# usbHub.net
KiCad netlist of a schematic drawn in EAGLE
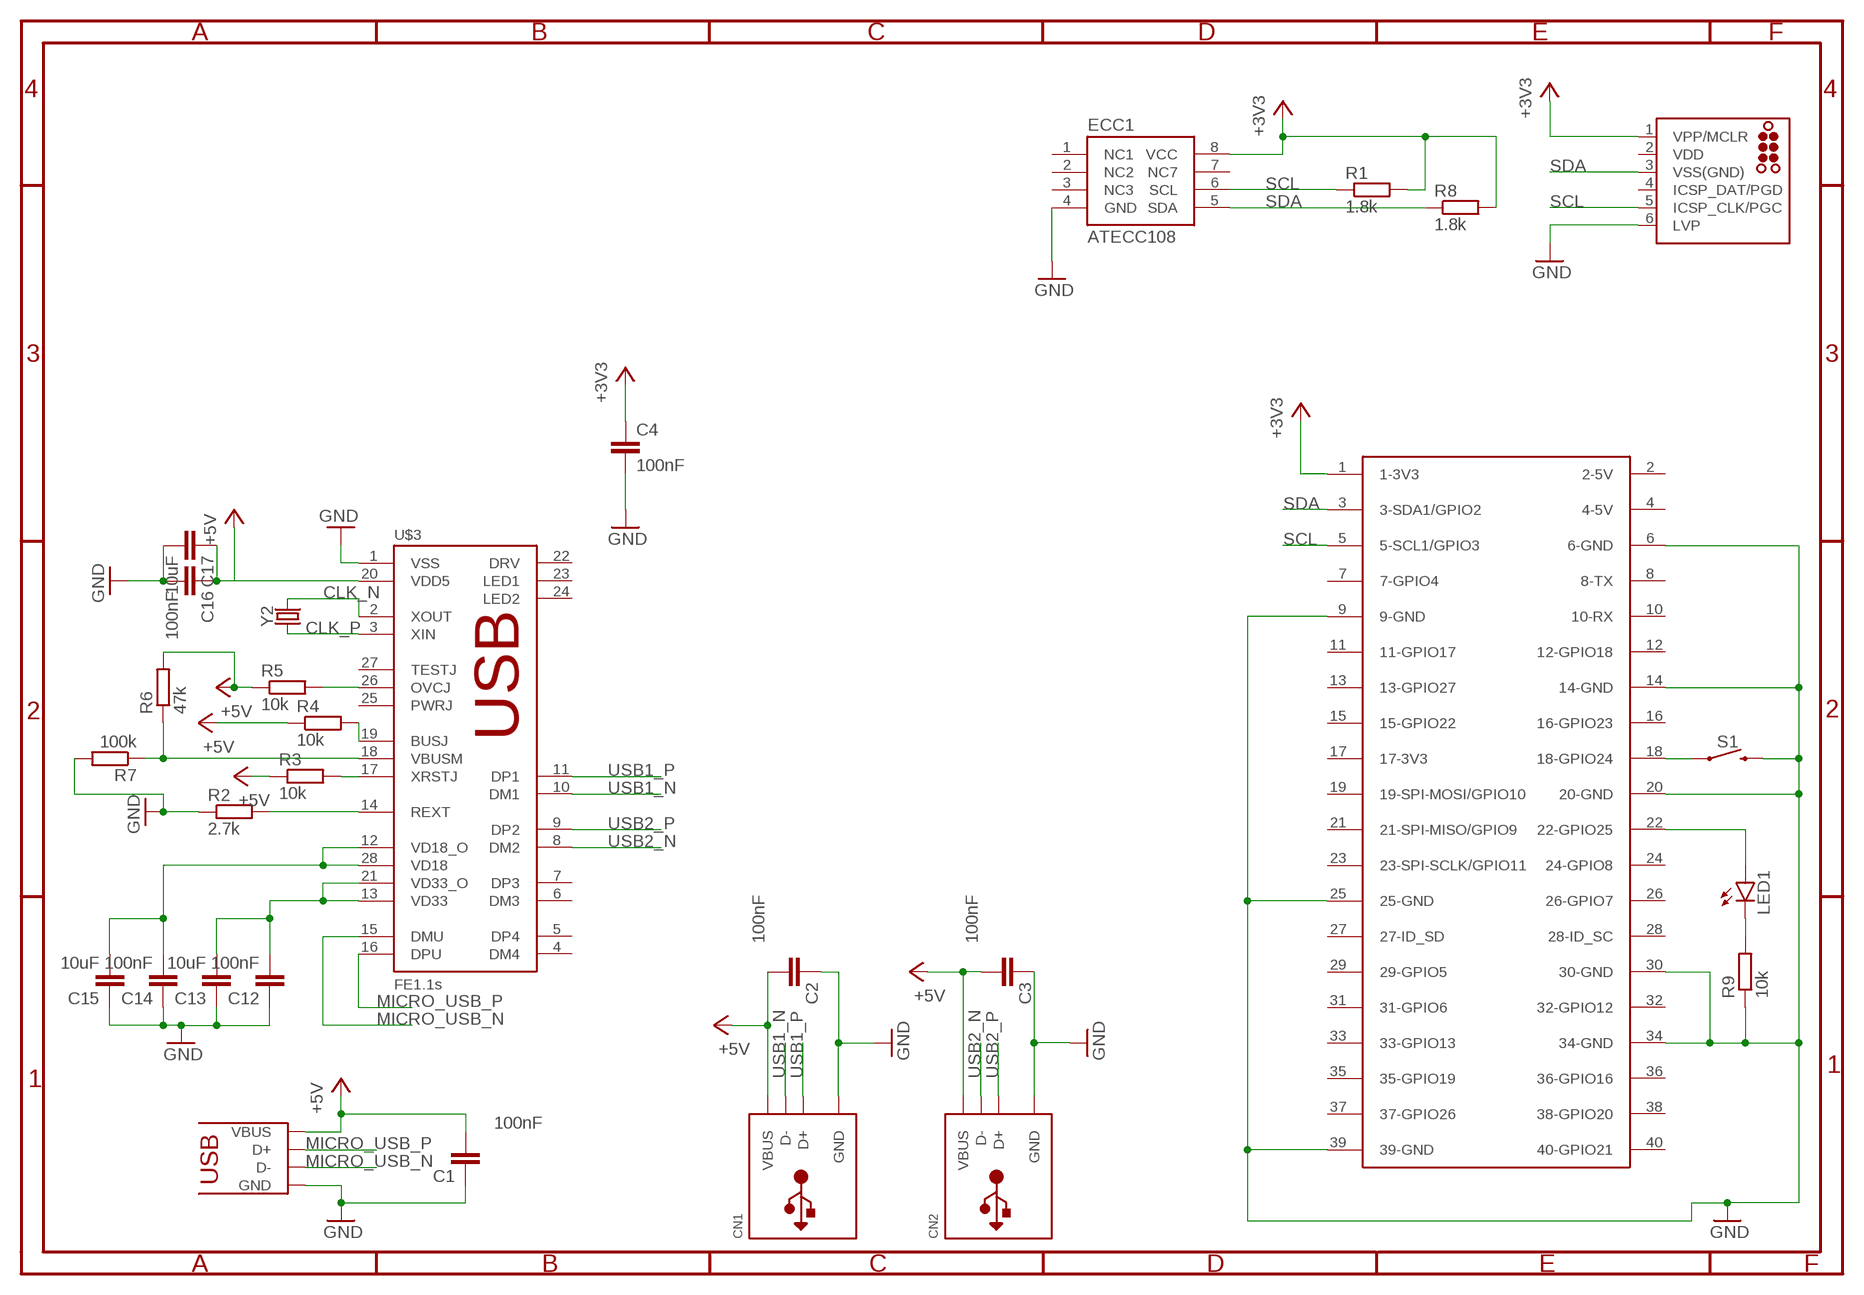
[diagram p0: schematic, sheet 1]

(export (version "E")
  (design (tool "Eeschema 10.0.6"))
  (components
    (comp (ref "C1")
      (value "100nF")
      (footprint "eagle-import:C0603")
      (libsource (lib "eagle-import") (part "C-EUC0603"))
    )
    (comp (ref "C2")
      (value "100nF")
      (footprint "eagle-import:C0603")
      (libsource (lib "eagle-import") (part "C-EUC0603"))
    )
    (comp (ref "C3")
      (value "100nF")
      (footprint "eagle-import:C0603")
      (libsource (lib "eagle-import") (part "C-EUC0603"))
    )
    (comp (ref "C4")
      (value "100nF")
      (footprint "eagle-import:C0603")
      (libsource (lib "eagle-import") (part "C-EUC0603"))
    )
    (comp (ref "C12")
      (value "100nF")
      (footprint "eagle-import:C0603")
      (libsource (lib "eagle-import") (part "C-EUC0603"))
    )
    (comp (ref "C13")
      (value "10uF")
      (footprint "eagle-import:C0603")
      (libsource (lib "eagle-import") (part "C-EUC0603"))
    )
    (comp (ref "C14")
      (value "100nF")
      (footprint "eagle-import:C0603")
      (libsource (lib "eagle-import") (part "C-EUC0603"))
    )
    (comp (ref "C15")
      (value "10uF")
      (footprint "eagle-import:C0603")
      (libsource (lib "eagle-import") (part "C-EUC0603"))
    )
    (comp (ref "C16")
      (value "100nF")
      (footprint "eagle-import:C0603")
      (libsource (lib "eagle-import") (part "C-EUC0603"))
    )
    (comp (ref "C17")
      (value "10uF")
      (footprint "eagle-import:C0603")
      (libsource (lib "eagle-import") (part "C-EUC0603"))
    )
    (comp (ref "CN1")
      (value "USB_TYPEAPTHFML")
      (footprint "eagle-import:USB_HOST-PTH")
      (libsource (lib "eagle-import") (part "USB_TYPEAPTHFML"))
    )
    (comp (ref "CN2")
      (value "USB_TYPEAPTHFML")
      (footprint "eagle-import:USB_HOST-PTH")
      (libsource (lib "eagle-import") (part "USB_TYPEAPTHFML"))
    )
    (comp (ref "ECC1")
      (value "ATECC108")
      (footprint "eagle-import:SO08")
      (libsource (lib "eagle-import") (part "ATECC108"))
    )
    (comp (ref "J1")
      (value "TC2030-MCP-NL")
      (footprint "eagle-import:TC2030-MCP-NL")
      (libsource (lib "eagle-import") (part "TC2030-MCP-NL"))
    )
    (comp (ref "LED1")
      (value "LEDCHIPLED_0603")
      (footprint "eagle-import:CHIPLED_0603")
      (libsource (lib "eagle-import") (part "LEDCHIPLED_0603"))
    )
    (comp (ref "R1")
      (value "1.8k")
      (footprint "eagle-import:R0603")
      (libsource (lib "eagle-import") (part "R-EU_R0603"))
    )
    (comp (ref "R2")
      (value "2.7k")
      (footprint "eagle-import:R0603")
      (libsource (lib "eagle-import") (part "R-EU_R0603"))
    )
    (comp (ref "R3")
      (value "10k")
      (footprint "eagle-import:R0603")
      (libsource (lib "eagle-import") (part "R-EU_R0603"))
    )
    (comp (ref "R4")
      (value "10k")
      (footprint "eagle-import:R0603")
      (libsource (lib "eagle-import") (part "R-EU_R0603"))
    )
    (comp (ref "R5")
      (value "10k")
      (footprint "eagle-import:R0603")
      (libsource (lib "eagle-import") (part "R-EU_R0603"))
    )
    (comp (ref "R6")
      (value "47k")
      (footprint "eagle-import:R0603")
      (libsource (lib "eagle-import") (part "R-EU_R0603"))
    )
    (comp (ref "R7")
      (value "100k")
      (footprint "eagle-import:R0603")
      (libsource (lib "eagle-import") (part "R-EU_R0603"))
    )
    (comp (ref "R8")
      (value "1.8k")
      (footprint "eagle-import:R0603")
      (libsource (lib "eagle-import") (part "R-EU_R0603"))
    )
    (comp (ref "R9")
      (value "10k")
      (footprint "eagle-import:R0603")
      (libsource (lib "eagle-import") (part "R-EU_R0603"))
    )
    (comp (ref "S1")
      (value "MOMENTARY-SWITCH-SPST-SMD-6.2MM-TALL")
      (footprint "eagle-import:TACTILE_SWITCH_SMD_6.2MM_TALL")
      (libsource (lib "eagle-import") (part "MOMENTARY-SWITCH-SPST-SMD-6.2MM-TALL"))
    )
    (comp (ref "U$1")
      (value "USB-MICROB")
      (footprint "eagle-import:USB-MICROB")
      (libsource (lib "eagle-import") (part "USB-MICROB"))
    )
    (comp (ref "U$3")
      (value "FE1.1S")
      (footprint "eagle-import:FE1.1S_SSOP-28")
      (libsource (lib "eagle-import") (part "FE1.1S"))
    )
    (comp (ref "U$4")
      (value "RASPBERRY-PI+HEADERONLY")
      (footprint "eagle-import:RASPBERRY-PI-PLUS-HEADERONLY")
      (libsource (lib "eagle-import") (part "RASPBERRY-PI+HEADERONLY"))
    )
    (comp (ref "Y2")
      (value "12mHZ")
      (footprint "eagle-import:HC49UP")
      (libsource (lib "eagle-import") (part "CRYSTALSMD-HC49UP"))
    )
  )
  (nets
    (net (code "1") (name "+3V3") (class "Default")
      (node (ref "C4") (pin "1") (pinfunction "1_1") (pintype "passive"))
      (node (ref "ECC1") (pin "8") (pinfunction "VCC_8") (pintype "power_in"))
      (node (ref "J1") (pin "1") (pinfunction "VPP/MCLR_1") (pintype "passive"))
      (node (ref "R1") (pin "2") (pinfunction "2_2") (pintype "passive"))
      (node (ref "R8") (pin "2") (pinfunction "2_2") (pintype "passive"))
      (node (ref "U$4") (pin "1") (pinfunction "1-3V3_1") (pintype "bidirectional"))
    )
    (net (code "2") (name "+5V") (class "Default")
      (node (ref "C1") (pin "2") (pinfunction "2_2") (pintype "passive"))
      (node (ref "C16") (pin "1") (pinfunction "1_1") (pintype "passive"))
      (node (ref "C17") (pin "1") (pinfunction "1_1") (pintype "passive"))
      (node (ref "C2") (pin "2") (pinfunction "2_2") (pintype "passive"))
      (node (ref "C3") (pin "2") (pinfunction "2_2") (pintype "passive"))
      (node (ref "CN1") (pin "VBUS") (pinfunction "VBUS_VBUS") (pintype "power_in"))
      (node (ref "CN2") (pin "VBUS") (pinfunction "VBUS_VBUS") (pintype "power_in"))
      (node (ref "R3") (pin "1") (pinfunction "1_1") (pintype "passive"))
      (node (ref "R4") (pin "1") (pinfunction "1_1") (pintype "passive"))
      (node (ref "R5") (pin "1") (pinfunction "1_1") (pintype "passive"))
      (node (ref "R6") (pin "2") (pinfunction "2_2") (pintype "passive"))
      (node (ref "U$1") (pin "VBUS") (pinfunction "VBUS_VBUS") (pintype "bidirectional"))
      (node (ref "U$3") (pin "20") (pinfunction "VDD5_20") (pintype "bidirectional"))
    )
    (net (code "3") (name "/CLK_N") (class "Default")
      (node (ref "U$3") (pin "2") (pinfunction "XOUT_2") (pintype "bidirectional"))
      (node (ref "Y2") (pin "2") (pinfunction "2_2") (pintype "passive"))
    )
    (net (code "4") (name "/CLK_P") (class "Default")
      (node (ref "U$3") (pin "3") (pinfunction "XIN_3") (pintype "bidirectional"))
      (node (ref "Y2") (pin "1") (pinfunction "1_1") (pintype "passive"))
    )
    (net (code "5") (name "/MICRO_USB_N") (class "Default")
      (node (ref "U$1") (pin "D-") (pinfunction "D-_D-") (pintype "bidirectional"))
      (node (ref "U$3") (pin "15") (pinfunction "DMU_15") (pintype "bidirectional"))
    )
    (net (code "6") (name "/MICRO_USB_P") (class "Default")
      (node (ref "U$1") (pin "D+") (pinfunction "D+_D+") (pintype "bidirectional"))
      (node (ref "U$3") (pin "16") (pinfunction "DPU_16") (pintype "bidirectional"))
    )
    (net (code "7") (name "/SCL") (class "Default")
      (node (ref "ECC1") (pin "6") (pinfunction "SCL_6") (pintype "bidirectional"))
      (node (ref "J1") (pin "5") (pinfunction "ICSP_CLK/PGC_5") (pintype "output"))
      (node (ref "R1") (pin "1") (pinfunction "1_1") (pintype "passive"))
      (node (ref "U$4") (pin "5") (pinfunction "5-SCL1/GPIO3_5") (pintype "bidirectional"))
    )
    (net (code "8") (name "/SDA") (class "Default")
      (node (ref "ECC1") (pin "5") (pinfunction "SDA_5") (pintype "bidirectional"))
      (node (ref "J1") (pin "3") (pinfunction "VSS(GND)_3") (pintype "power_in"))
      (node (ref "R8") (pin "1") (pinfunction "1_1") (pintype "passive"))
      (node (ref "U$4") (pin "3") (pinfunction "3-SDA1/GPIO2_3") (pintype "bidirectional"))
    )
    (net (code "9") (name "/USB1_N") (class "Default")
      (node (ref "CN1") (pin "D-") (pinfunction "D-_D-") (pintype "bidirectional"))
      (node (ref "U$3") (pin "10") (pinfunction "DM1_10") (pintype "bidirectional"))
    )
    (net (code "10") (name "/USB1_P") (class "Default")
      (node (ref "CN1") (pin "D+") (pinfunction "D+_D+") (pintype "bidirectional"))
      (node (ref "U$3") (pin "11") (pinfunction "DP1_11") (pintype "bidirectional"))
    )
    (net (code "11") (name "/USB2_N") (class "Default")
      (node (ref "CN2") (pin "D-") (pinfunction "D-_D-") (pintype "bidirectional"))
      (node (ref "U$3") (pin "8") (pinfunction "DM2_8") (pintype "bidirectional"))
    )
    (net (code "12") (name "/USB2_P") (class "Default")
      (node (ref "CN2") (pin "D+") (pinfunction "D+_D+") (pintype "bidirectional"))
      (node (ref "U$3") (pin "9") (pinfunction "DP2_9") (pintype "bidirectional"))
    )
    (net (code "13") (name "/VDD") (class "Default")
      (node (ref "J1") (pin "2") (pinfunction "VDD_2") (pintype "power_in"))
    )
    (net (code "14") (name "GND") (class "Default")
      (node (ref "C1") (pin "1") (pinfunction "1_1") (pintype "passive"))
      (node (ref "C12") (pin "1") (pinfunction "1_1") (pintype "passive"))
      (node (ref "C13") (pin "1") (pinfunction "1_1") (pintype "passive"))
      (node (ref "C14") (pin "1") (pinfunction "1_1") (pintype "passive"))
      (node (ref "C15") (pin "1") (pinfunction "1_1") (pintype "passive"))
      (node (ref "C16") (pin "2") (pinfunction "2_2") (pintype "passive"))
      (node (ref "C17") (pin "2") (pinfunction "2_2") (pintype "passive"))
      (node (ref "C2") (pin "1") (pinfunction "1_1") (pintype "passive"))
      (node (ref "C3") (pin "1") (pinfunction "1_1") (pintype "passive"))
      (node (ref "C4") (pin "2") (pinfunction "2_2") (pintype "passive"))
      (node (ref "CN1") (pin "GND") (pinfunction "GND_GND") (pintype "power_in"))
      (node (ref "CN2") (pin "GND") (pinfunction "GND_GND") (pintype "power_in"))
      (node (ref "ECC1") (pin "4") (pinfunction "GND_4") (pintype "power_in"))
      (node (ref "J1") (pin "6") (pinfunction "LVP_6") (pintype "bidirectional"))
      (node (ref "R2") (pin "1") (pinfunction "1_1") (pintype "passive"))
      (node (ref "R7") (pin "2") (pinfunction "2_2") (pintype "passive"))
      (node (ref "R9") (pin "1") (pinfunction "1_1") (pintype "passive"))
      (node (ref "S1") (pin "B2") (pinfunction "2_B2") (pintype "passive"))
      (node (ref "U$1") (pin "GND") (pinfunction "GND_GND") (pintype "bidirectional"))
      (node (ref "U$1") (pin "MT1") (pinfunction "GND_MT1") (pintype "bidirectional"))
      (node (ref "U$1") (pin "MT2") (pinfunction "GND_MT2") (pintype "bidirectional"))
      (node (ref "U$1") (pin "P$1") (pinfunction "GND_P$1") (pintype "bidirectional"))
      (node (ref "U$1") (pin "P$2") (pinfunction "GND_P$2") (pintype "bidirectional"))
      (node (ref "U$1") (pin "P$3") (pinfunction "GND_P$3") (pintype "bidirectional"))
      (node (ref "U$1") (pin "P$4") (pinfunction "GND_P$4") (pintype "bidirectional"))
      (node (ref "U$3") (pin "1") (pinfunction "VSS_1") (pintype "bidirectional"))
      (node (ref "U$4") (pin "14") (pinfunction "14-GND_14") (pintype "bidirectional"))
      (node (ref "U$4") (pin "20") (pinfunction "20-GND_20") (pintype "bidirectional"))
      (node (ref "U$4") (pin "25") (pinfunction "25-GND_25") (pintype "bidirectional"))
      (node (ref "U$4") (pin "30") (pinfunction "30-GND_30") (pintype "bidirectional"))
      (node (ref "U$4") (pin "34") (pinfunction "34-GND_34") (pintype "bidirectional"))
      (node (ref "U$4") (pin "39") (pinfunction "39-GND_39") (pintype "bidirectional"))
      (node (ref "U$4") (pin "6") (pinfunction "6-GND_6") (pintype "bidirectional"))
      (node (ref "U$4") (pin "9") (pinfunction "9-GND_9") (pintype "bidirectional"))
    )
    (net (code "15") (name "Net-(LED1-PadC)") (class "Default")
      (node (ref "LED1") (pin "C") (pinfunction "C_C") (pintype "passive"))
      (node (ref "R9") (pin "2") (pinfunction "2_2") (pintype "passive"))
    )
    (net (code "16") (name "Net-(S1-1)") (class "Default")
      (node (ref "S1") (pin "A2") (pinfunction "1_A2") (pintype "passive"))
      (node (ref "U$4") (pin "18") (pinfunction "18-GPIO24_18") (pintype "bidirectional"))
    )
    (net (code "17") (name "Net-(U$3-BUSJ)") (class "Default")
      (node (ref "R4") (pin "2") (pinfunction "2_2") (pintype "passive"))
      (node (ref "U$3") (pin "19") (pinfunction "BUSJ_19") (pintype "bidirectional"))
    )
    (net (code "18") (name "Net-(U$3-OVCJ)") (class "Default")
      (node (ref "R5") (pin "2") (pinfunction "2_2") (pintype "passive"))
      (node (ref "U$3") (pin "26") (pinfunction "OVCJ_26") (pintype "bidirectional"))
    )
    (net (code "19") (name "Net-(U$3-REXT)") (class "Default")
      (node (ref "R2") (pin "2") (pinfunction "2_2") (pintype "passive"))
      (node (ref "U$3") (pin "14") (pinfunction "REXT_14") (pintype "bidirectional"))
    )
    (net (code "20") (name "Net-(U$3-VBUSM)") (class "Default")
      (node (ref "R6") (pin "1") (pinfunction "1_1") (pintype "passive"))
      (node (ref "R7") (pin "1") (pinfunction "1_1") (pintype "passive"))
      (node (ref "U$3") (pin "18") (pinfunction "VBUSM_18") (pintype "bidirectional"))
    )
    (net (code "21") (name "Net-(U$3-VD18)") (class "Default")
      (node (ref "C14") (pin "2") (pinfunction "2_2") (pintype "passive"))
      (node (ref "C15") (pin "2") (pinfunction "2_2") (pintype "passive"))
      (node (ref "U$3") (pin "12") (pinfunction "VD18_O_12") (pintype "bidirectional"))
      (node (ref "U$3") (pin "28") (pinfunction "VD18_28") (pintype "bidirectional"))
    )
    (net (code "22") (name "Net-(U$3-VD33)") (class "Default")
      (node (ref "C12") (pin "2") (pinfunction "2_2") (pintype "passive"))
      (node (ref "C13") (pin "2") (pinfunction "2_2") (pintype "passive"))
      (node (ref "U$3") (pin "13") (pinfunction "VD33_13") (pintype "bidirectional"))
      (node (ref "U$3") (pin "21") (pinfunction "VD33_O_21") (pintype "bidirectional"))
    )
    (net (code "23") (name "Net-(U$3-XRSTJ)") (class "Default")
      (node (ref "R3") (pin "2") (pinfunction "2_2") (pintype "passive"))
      (node (ref "U$3") (pin "17") (pinfunction "XRSTJ_17") (pintype "bidirectional"))
    )
    (net (code "24") (name "Net-(U$4-22-GPIO25)") (class "Default")
      (node (ref "LED1") (pin "A") (pinfunction "A_A") (pintype "passive"))
      (node (ref "U$4") (pin "22") (pinfunction "22-GPIO25_22") (pintype "bidirectional"))
    )
    (net (code "25") (name "unconnected-(ECC1-NC1-Pad1)") (class "Default")
      (node (ref "ECC1") (pin "1") (pinfunction "NC1_1") (pintype "bidirectional"))
    )
    (net (code "26") (name "unconnected-(ECC1-NC2-Pad2)") (class "Default")
      (node (ref "ECC1") (pin "2") (pinfunction "NC2_2") (pintype "no_connect"))
    )
    (net (code "27") (name "unconnected-(ECC1-NC3-Pad3)") (class "Default")
      (node (ref "ECC1") (pin "3") (pinfunction "NC3_3") (pintype "no_connect"))
    )
    (net (code "28") (name "unconnected-(ECC1-NC7-Pad7)") (class "Default")
      (node (ref "ECC1") (pin "7") (pinfunction "NC7_7") (pintype "no_connect"))
    )
    (net (code "29") (name "unconnected-(J1-ICSP_DAT{slash}PGD-Pad4)") (class "Default")
      (node (ref "J1") (pin "4") (pinfunction "ICSP_DAT/PGD_4") (pintype "bidirectional"))
    )
    (net (code "30") (name "unconnected-(U$3-DM3-Pad6)") (class "Default")
      (node (ref "U$3") (pin "6") (pinfunction "DM3_6") (pintype "bidirectional"))
    )
    (net (code "31") (name "unconnected-(U$3-DM4-Pad4)") (class "Default")
      (node (ref "U$3") (pin "4") (pinfunction "DM4_4") (pintype "bidirectional"))
    )
    (net (code "32") (name "unconnected-(U$3-DP3-Pad7)") (class "Default")
      (node (ref "U$3") (pin "7") (pinfunction "DP3_7") (pintype "bidirectional"))
    )
    (net (code "33") (name "unconnected-(U$3-DP4-Pad5)") (class "Default")
      (node (ref "U$3") (pin "5") (pinfunction "DP4_5") (pintype "bidirectional"))
    )
    (net (code "34") (name "unconnected-(U$3-DRV-Pad22)") (class "Default")
      (node (ref "U$3") (pin "22") (pinfunction "DRV_22") (pintype "bidirectional"))
    )
    (net (code "35") (name "unconnected-(U$3-LED1-Pad23)") (class "Default")
      (node (ref "U$3") (pin "23") (pinfunction "LED1_23") (pintype "bidirectional"))
    )
    (net (code "36") (name "unconnected-(U$3-LED2-Pad24)") (class "Default")
      (node (ref "U$3") (pin "24") (pinfunction "LED2_24") (pintype "bidirectional"))
    )
    (net (code "37") (name "unconnected-(U$3-PWRJ-Pad25)") (class "Default")
      (node (ref "U$3") (pin "25") (pinfunction "PWRJ_25") (pintype "bidirectional"))
    )
    (net (code "38") (name "unconnected-(U$3-TESTJ-Pad27)") (class "Default")
      (node (ref "U$3") (pin "27") (pinfunction "TESTJ_27") (pintype "bidirectional"))
    )
    (net (code "39") (name "unconnected-(U$4-2-5V-Pad2)") (class "Default")
      (node (ref "U$4") (pin "2") (pinfunction "2-5V_2") (pintype "bidirectional"))
    )
    (net (code "40") (name "unconnected-(U$4-4-5V-Pad4)") (class "Default")
      (node (ref "U$4") (pin "4") (pinfunction "4-5V_4") (pintype "bidirectional"))
    )
    (net (code "41") (name "unconnected-(U$4-7-GPIO4-Pad7)") (class "Default")
      (node (ref "U$4") (pin "7") (pinfunction "7-GPIO4_7") (pintype "bidirectional"))
    )
    (net (code "42") (name "unconnected-(U$4-8-TX-Pad8)") (class "Default")
      (node (ref "U$4") (pin "8") (pinfunction "8-TX_8") (pintype "bidirectional"))
    )
    (net (code "43") (name "unconnected-(U$4-10-RX-Pad10)") (class "Default")
      (node (ref "U$4") (pin "10") (pinfunction "10-RX_10") (pintype "bidirectional"))
    )
    (net (code "44") (name "unconnected-(U$4-11-GPIO17-Pad11)") (class "Default")
      (node (ref "U$4") (pin "11") (pinfunction "11-GPIO17_11") (pintype "bidirectional"))
    )
    (net (code "45") (name "unconnected-(U$4-12-GPIO18-Pad12)") (class "Default")
      (node (ref "U$4") (pin "12") (pinfunction "12-GPIO18_12") (pintype "bidirectional"))
    )
    (net (code "46") (name "unconnected-(U$4-13-GPIO27-Pad13)") (class "Default")
      (node (ref "U$4") (pin "13") (pinfunction "13-GPIO27_13") (pintype "bidirectional"))
    )
    (net (code "47") (name "unconnected-(U$4-15-GPIO22-Pad15)") (class "Default")
      (node (ref "U$4") (pin "15") (pinfunction "15-GPIO22_15") (pintype "bidirectional"))
    )
    (net (code "48") (name "unconnected-(U$4-16-GPIO23-Pad16)") (class "Default")
      (node (ref "U$4") (pin "16") (pinfunction "16-GPIO23_16") (pintype "bidirectional"))
    )
    (net (code "49") (name "unconnected-(U$4-17-3V3-Pad17)") (class "Default")
      (node (ref "U$4") (pin "17") (pinfunction "17-3V3_17") (pintype "bidirectional"))
    )
    (net (code "50") (name "unconnected-(U$4-19-SPI-MOSI{slash}GPIO10-Pad19)") (class "Default")
      (node (ref "U$4") (pin "19") (pinfunction "19-SPI-MOSI/GPIO10_19") (pintype "bidirectional"))
    )
    (net (code "51") (name "unconnected-(U$4-21-SPI-MISO{slash}GPIO9-Pad21)") (class "Default")
      (node (ref "U$4") (pin "21") (pinfunction "21-SPI-MISO/GPIO9_21") (pintype "bidirectional"))
    )
    (net (code "52") (name "unconnected-(U$4-23-SPI-SCLK{slash}GPIO11-Pad23)") (class "Default")
      (node (ref "U$4") (pin "23") (pinfunction "23-SPI-SCLK/GPIO11_23") (pintype "bidirectional"))
    )
    (net (code "53") (name "unconnected-(U$4-24-GPIO8-Pad24)") (class "Default")
      (node (ref "U$4") (pin "24") (pinfunction "24-GPIO8_24") (pintype "bidirectional"))
    )
    (net (code "54") (name "unconnected-(U$4-26-GPIO7-Pad26)") (class "Default")
      (node (ref "U$4") (pin "26") (pinfunction "26-GPIO7_26") (pintype "bidirectional"))
    )
    (net (code "55") (name "unconnected-(U$4-27-ID_SD-Pad27)") (class "Default")
      (node (ref "U$4") (pin "27") (pinfunction "27-ID_SD_27") (pintype "bidirectional"))
    )
    (net (code "56") (name "unconnected-(U$4-28-ID_SC-Pad28)") (class "Default")
      (node (ref "U$4") (pin "28") (pinfunction "28-ID_SC_28") (pintype "bidirectional"))
    )
    (net (code "57") (name "unconnected-(U$4-29-GPIO5-Pad29)") (class "Default")
      (node (ref "U$4") (pin "29") (pinfunction "29-GPIO5_29") (pintype "bidirectional"))
    )
    (net (code "58") (name "unconnected-(U$4-31-GPIO6-Pad31)") (class "Default")
      (node (ref "U$4") (pin "31") (pinfunction "31-GPIO6_31") (pintype "bidirectional"))
    )
    (net (code "59") (name "unconnected-(U$4-32-GPIO12-Pad32)") (class "Default")
      (node (ref "U$4") (pin "32") (pinfunction "32-GPIO12_32") (pintype "bidirectional"))
    )
    (net (code "60") (name "unconnected-(U$4-33-GPIO13-Pad33)") (class "Default")
      (node (ref "U$4") (pin "33") (pinfunction "33-GPIO13_33") (pintype "bidirectional"))
    )
    (net (code "61") (name "unconnected-(U$4-35-GPIO19-Pad35)") (class "Default")
      (node (ref "U$4") (pin "35") (pinfunction "35-GPIO19_35") (pintype "bidirectional"))
    )
    (net (code "62") (name "unconnected-(U$4-36-GPIO16-Pad36)") (class "Default")
      (node (ref "U$4") (pin "36") (pinfunction "36-GPIO16_36") (pintype "bidirectional"))
    )
    (net (code "63") (name "unconnected-(U$4-37-GPIO26-Pad37)") (class "Default")
      (node (ref "U$4") (pin "37") (pinfunction "37-GPIO26_37") (pintype "bidirectional"))
    )
    (net (code "64") (name "unconnected-(U$4-38-GPIO20-Pad38)") (class "Default")
      (node (ref "U$4") (pin "38") (pinfunction "38-GPIO20_38") (pintype "bidirectional"))
    )
    (net (code "65") (name "unconnected-(U$4-40-GPIO21-Pad40)") (class "Default")
      (node (ref "U$4") (pin "40") (pinfunction "40-GPIO21_40") (pintype "bidirectional"))
    )
  )
)
